# Sheet1.net
KiCad netlist of a schematic drawn in Altium Designer
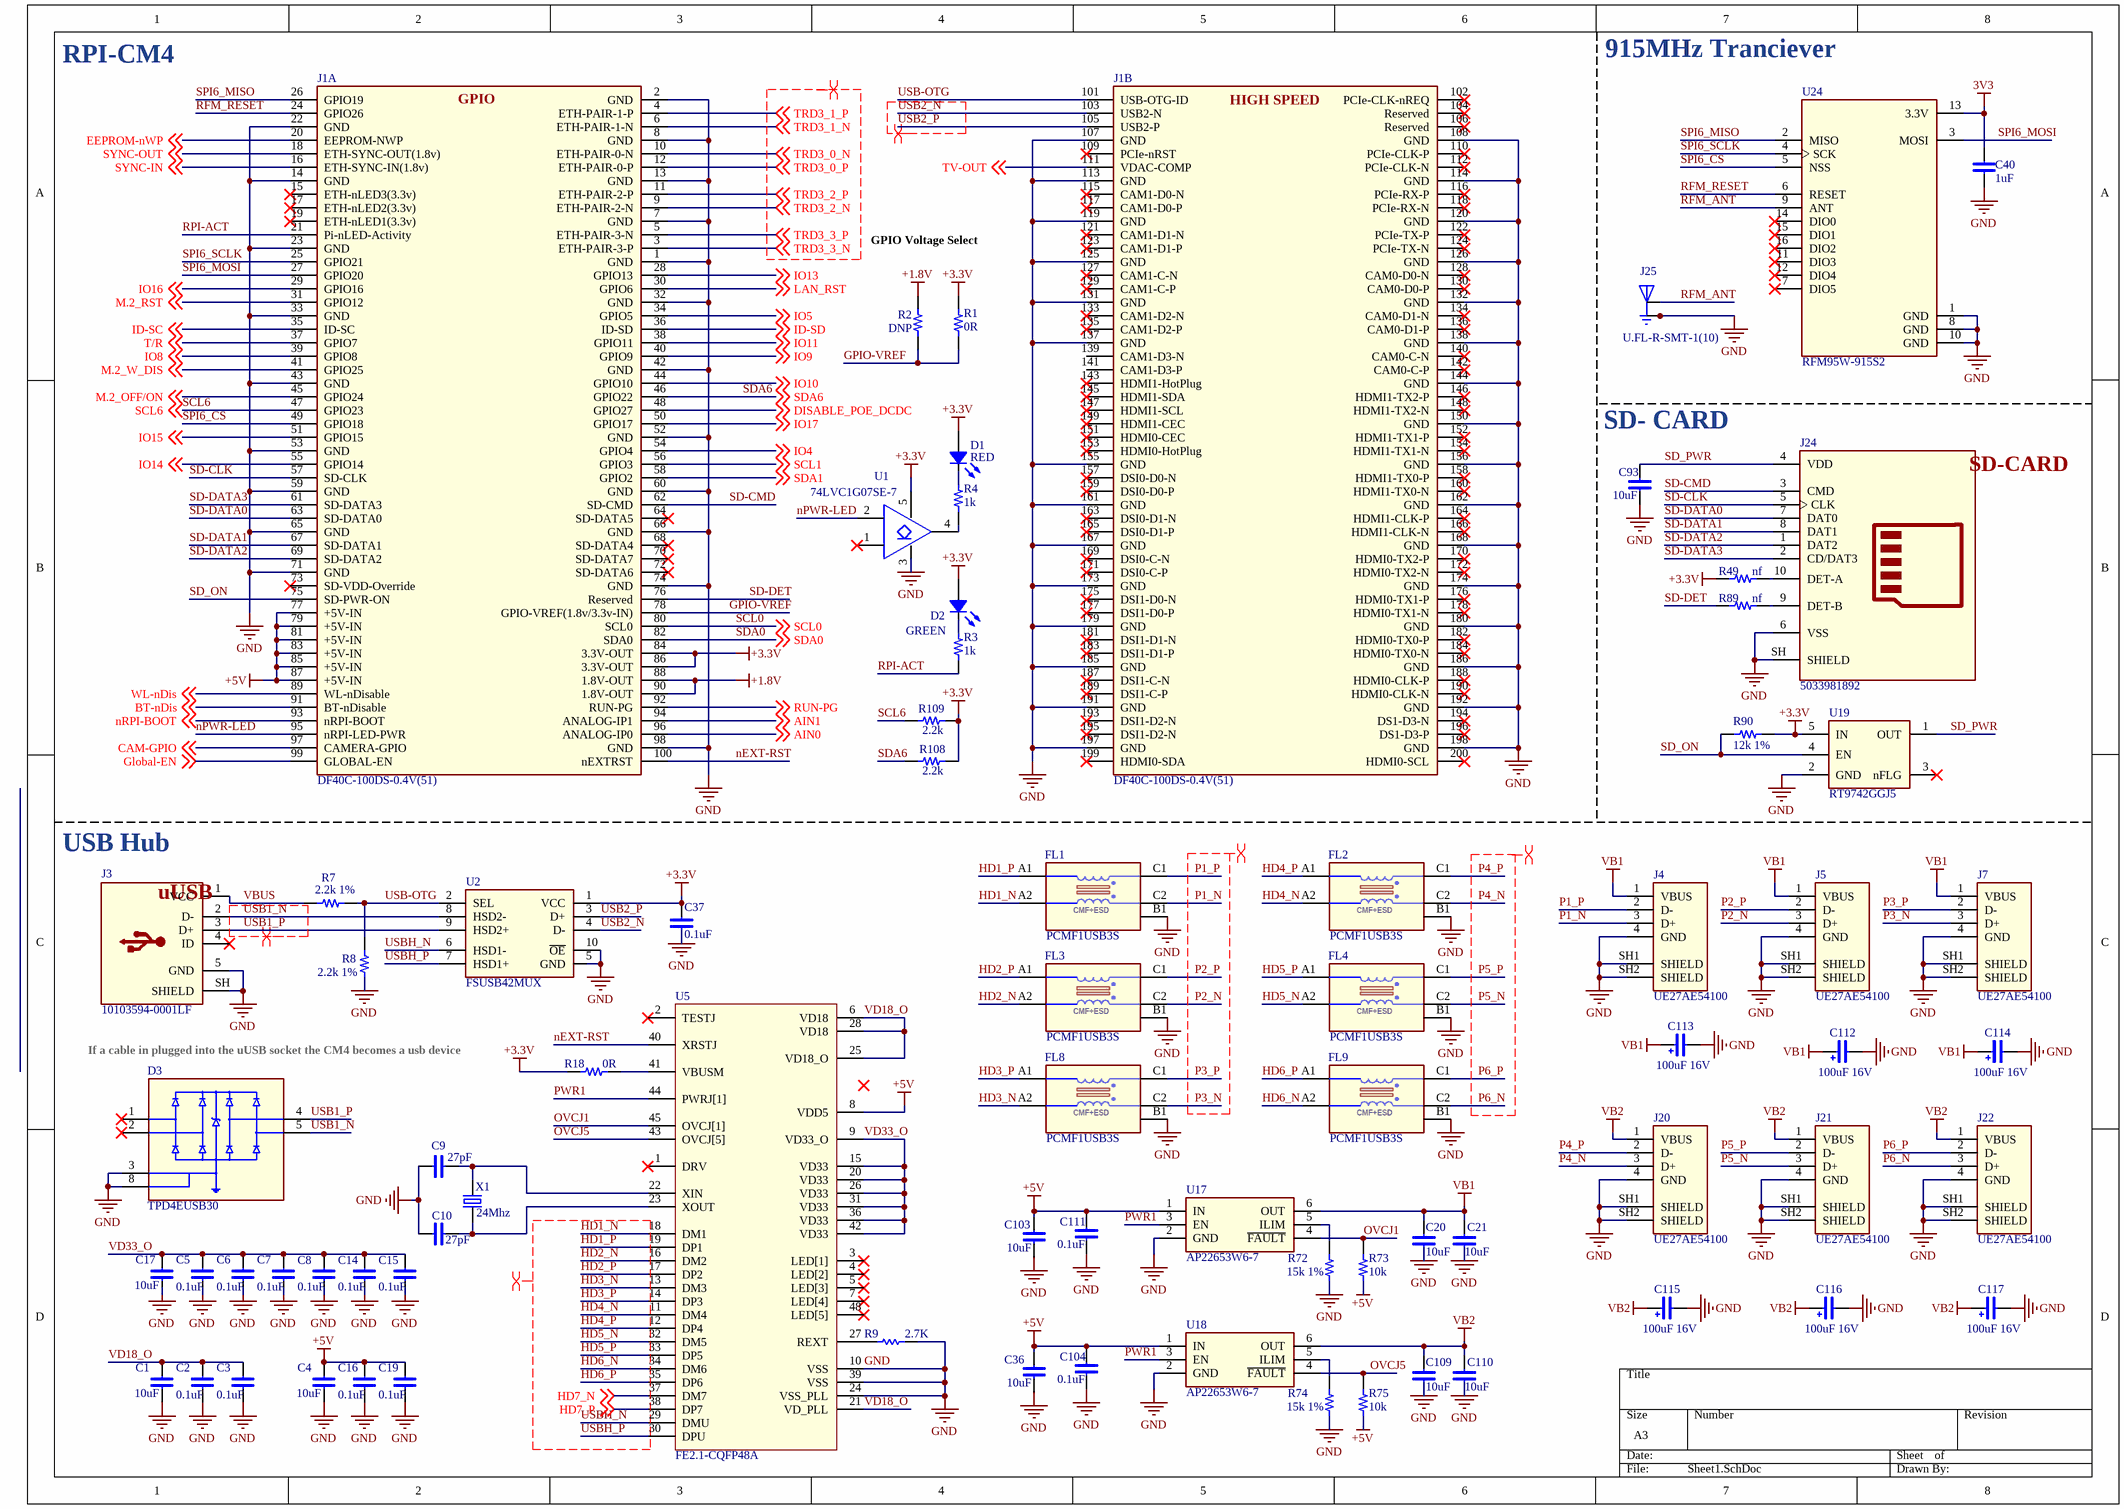
[diagram p0: Sheet1.SchDoc]

(export (version "E")
  (design (tool "Eeschema 10.0.6"))
  (components
    (comp (ref "C1")
      (value "10uF")
      (footprint "C-0603/1608")
      (description "CAP CER 10UF 10V X7R 0805")
      (fields (field (name "MFR. PART NO.") "GRM21BR71A106KA73K"))
      (libsource (lib "Custom_Library") (part "Capacitor-NonPolar"))
    )
    (comp (ref "C2")
      (value "0.1uF")
      (footprint "C-0402/1005")
      (description "CAP CER 0.1UF 16V X7R 0402")
      (fields (field (name "MFR. PART NO.") "GCM155R71C104KA55D"))
      (libsource (lib "Custom_Library") (part "Capacitor-NonPolar"))
    )
    (comp (ref "C3")
      (value "0.1uF")
      (footprint "C-0402/1005")
      (description "CAP CER 0.1UF 16V X7R 0402")
      (fields (field (name "MFR. PART NO.") "GCM155R71C104KA55D"))
      (libsource (lib "Custom_Library") (part "Capacitor-NonPolar"))
    )
    (comp (ref "C4")
      (value "10uF")
      (footprint "C-0603/1608")
      (description "CAP CER 10UF 10V X7R 0805")
      (fields (field (name "MFR. PART NO.") "GRM21BR71A106KA73K"))
      (libsource (lib "Custom_Library") (part "Capacitor-NonPolar"))
    )
    (comp (ref "C5")
      (value "0.1uF")
      (footprint "C-0402/1005")
      (description "CAP CER 0.1UF 16V X7R 0402")
      (fields (field (name "MFR. PART NO.") "GCM155R71C104KA55D"))
      (libsource (lib "Custom_Library") (part "Capacitor-NonPolar"))
    )
    (comp (ref "C6")
      (value "0.1uF")
      (footprint "C-0402/1005")
      (description "CAP CER 0.1UF 16V X7R 0402")
      (fields (field (name "MFR. PART NO.") "GCM155R71C104KA55D"))
      (libsource (lib "Custom_Library") (part "Capacitor-NonPolar"))
    )
    (comp (ref "C7")
      (value "0.1uF")
      (footprint "C-0402/1005")
      (description "CAP CER 0.1UF 16V X7R 0402")
      (fields (field (name "MFR. PART NO.") "GCM155R71C104KA55D"))
      (libsource (lib "Custom_Library") (part "Capacitor-NonPolar"))
    )
    (comp (ref "C8")
      (value "0.1uF")
      (footprint "C-0402/1005")
      (description "CAP CER 0.1UF 16V X7R 0402")
      (fields (field (name "MFR. PART NO.") "GCM155R71C104KA55D"))
      (libsource (lib "Custom_Library") (part "Capacitor-NonPolar"))
    )
    (comp (ref "C9")
      (value "27pF")
      (footprint "C-0402/1005")
      (description "CAP CER 27PF 50V CH 0402")
      (fields (field (name "MFR. PART NO.") "UMK105CH270JVHF"))
      (libsource (lib "DVT2 Library") (part "Capacitor-NonPolar"))
    )
    (comp (ref "C10")
      (value "27pF")
      (footprint "C-0402/1005")
      (description "CAP CER 27PF 50V CH 0402")
      (fields (field (name "MFR. PART NO.") "UMK105CH270JVHF"))
      (libsource (lib "DVT2 Library") (part "Capacitor-NonPolar"))
    )
    (comp (ref "C14")
      (value "0.1uF")
      (footprint "C-0402/1005")
      (description "CAP CER 0.1UF 16V X7R 0402")
      (fields (field (name "MFR. PART NO.") "GCM155R71C104KA55D"))
      (libsource (lib "Custom_Library") (part "Capacitor-NonPolar"))
    )
    (comp (ref "C15")
      (value "0.1uF")
      (footprint "C-0402/1005")
      (description "CAP CER 0.1UF 16V X7R 0402")
      (fields (field (name "MFR. PART NO.") "GCM155R71C104KA55D"))
      (libsource (lib "Custom_Library") (part "Capacitor-NonPolar"))
    )
    (comp (ref "C16")
      (value "0.1uF")
      (footprint "C-0402/1005")
      (description "CAP CER 0.1UF 16V X7R 0402")
      (fields (field (name "MFR. PART NO.") "GCM155R71C104KA55D"))
      (libsource (lib "Custom_Library") (part "Capacitor-NonPolar"))
    )
    (comp (ref "C17")
      (value "10uF")
      (footprint "C-0603/1608")
      (description "CAP CER 10UF 10V X7R 0805")
      (fields (field (name "MFR. PART NO.") "GRM21BR71A106KA73K"))
      (libsource (lib "Custom_Library") (part "Capacitor-NonPolar"))
    )
    (comp (ref "C19")
      (value "0.1uF")
      (footprint "C-0402/1005")
      (description "CAP CER 0.1UF 16V X7R 0402")
      (fields (field (name "MFR. PART NO.") "GCM155R71C104KA55D"))
      (libsource (lib "Custom_Library") (part "Capacitor-NonPolar"))
    )
    (comp (ref "C20")
      (value "10uF")
      (footprint "C-0603/1608")
      (description "CAP CER 10UF 10V X7R 0805")
      (fields (field (name "MFR. PART NO.") "GRM21BR71A106KA73K"))
      (libsource (lib "Custom_Library") (part "Capacitor-NonPolar"))
    )
    (comp (ref "C21")
      (value "10uF")
      (footprint "C-0603/1608")
      (description "CAP CER 10UF 10V X7R 0805")
      (fields (field (name "MFR. PART NO.") "GRM21BR71A106KA73K"))
      (libsource (lib "Custom_Library") (part "Capacitor-NonPolar"))
    )
    (comp (ref "C36")
      (value "10uF")
      (footprint "C-0603/1608")
      (description "CAP CER 10UF 10V X7R 0805")
      (fields (field (name "MFR. PART NO.") "GRM21BR71A106KA73K"))
      (libsource (lib "Custom_Library") (part "Capacitor-NonPolar"))
    )
    (comp (ref "C37")
      (value "0.1uF")
      (footprint "C-0402/1005")
      (description "CAP CER 0.1UF 16V X7R 0402")
      (fields (field (name "MFR. PART NO.") "GCM155R71C104KA55D"))
      (libsource (lib "Custom_Library") (part "Capacitor-NonPolar"))
    )
    (comp (ref "C40")
      (value "1uF")
      (footprint "C-0402/1005")
      (description "CAP CER 0.1UF 50V X7R 0402")
      (fields (field (name "MFR. PART NO.") "UMK105B7104KV-FR"))
      (libsource (lib "Custom_Library") (part "Capacitor-NonPolar"))
    )
    (comp (ref "C93")
      (value "10uF")
      (footprint "C-0805/2012")
      (description "CAP CER 10UF 10V X7R 0805")
      (fields (field (name "MFR. PART NO.") "GRM21BR71A106KA73K"))
      (libsource (lib "Custom_Library") (part "Capacitor-NonPolar"))
    )
    (comp (ref "C103")
      (value "10uF")
      (footprint "C-0603/1608")
      (description "CAP CER 10UF 10V X7R 0805")
      (fields (field (name "MFR. PART NO.") "GRM21BR71A106KA73K"))
      (libsource (lib "Custom_Library") (part "Capacitor-NonPolar"))
    )
    (comp (ref "C104")
      (value "0.1uF")
      (footprint "C-0402/1005")
      (description "CAP CER 0.1UF 16V X7R 0402")
      (fields (field (name "MFR. PART NO.") "GCM155R71C104KA55D"))
      (libsource (lib "Custom_Library") (part "Capacitor-NonPolar"))
    )
    (comp (ref "C109")
      (value "10uF")
      (footprint "C-0603/1608")
      (description "CAP CER 10UF 10V X7R 0805")
      (fields (field (name "MFR. PART NO.") "GRM21BR71A106KA73K"))
      (libsource (lib "Custom_Library") (part "Capacitor-NonPolar"))
    )
    (comp (ref "C110")
      (value "10uF")
      (footprint "C-0603/1608")
      (description "CAP CER 10UF 10V X7R 0805")
      (fields (field (name "MFR. PART NO.") "GRM21BR71A106KA73K"))
      (libsource (lib "Custom_Library") (part "Capacitor-NonPolar"))
    )
    (comp (ref "C111")
      (value "0.1uF")
      (footprint "C-0402/1005")
      (description "CAP CER 0.1UF 16V X7R 0402")
      (fields (field (name "MFR. PART NO.") "GCM155R71C104KA55D"))
      (libsource (lib "Custom_Library") (part "Capacitor-NonPolar"))
    )
    (comp (ref "C112")
      (value "100uF 16V")
      (footprint "CAP-TAN-2312")
      (description "CAP TANT 10UF 10% 16V 1206")
      (fields (field (name "MFR. PART NO.") "F931C106KAAAJ6"))
      (libsource (lib "Custom_Library") (part "Capacitor-Polar"))
    )
    (comp (ref "C113")
      (value "100uF 16V")
      (footprint "CAP-TAN-2312")
      (description "CAP TANT 10UF 10% 16V 1206")
      (fields (field (name "MFR. PART NO.") "F931C106KAAAJ6"))
      (libsource (lib "Custom_Library") (part "Capacitor-Polar"))
    )
    (comp (ref "C114")
      (value "100uF 16V")
      (footprint "CAP-TAN-2312")
      (description "CAP TANT 10UF 10% 16V 1206")
      (fields (field (name "MFR. PART NO.") "F931C106KAAAJ6"))
      (libsource (lib "Custom_Library") (part "Capacitor-Polar"))
    )
    (comp (ref "C115")
      (value "100uF 16V")
      (footprint "CAP-TAN-2312")
      (description "CAP TANT 10UF 10% 16V 1206")
      (fields (field (name "MFR. PART NO.") "F931C106KAAAJ6"))
      (libsource (lib "Custom_Library") (part "Capacitor-Polar"))
    )
    (comp (ref "C116")
      (value "100uF 16V")
      (footprint "CAP-TAN-2312")
      (description "CAP TANT 10UF 10% 16V 1206")
      (fields (field (name "MFR. PART NO.") "F931C106KAAAJ6"))
      (libsource (lib "Custom_Library") (part "Capacitor-Polar"))
    )
    (comp (ref "C117")
      (value "100uF 16V")
      (footprint "CAP-TAN-2312")
      (description "CAP TANT 10UF 10% 16V 1206")
      (fields (field (name "MFR. PART NO.") "F931C106KAAAJ6"))
      (libsource (lib "Custom_Library") (part "Capacitor-Polar"))
    )
    (comp (ref "D1")
      (value "RED")
      (footprint "LED-0603-RED")
      (description "LED RED CLEAR CHIP SMD R/A")
      (fields (field (name "MFR. PART NO.") "LTST-S270KRKT"))
      (libsource (lib "Diodes") (part "LED SMD"))
    )
    (comp (ref "D2")
      (value "GREEN")
      (footprint "LED-0603-Green")
      (description "LED GREEN CLEAR CHIP SMD R/A")
      (fields (field (name "MFR. PART NO.") "LTST-S270KGKT"))
      (libsource (lib "Diodes") (part "LED SMD"))
    )
    (comp (ref "D3")
      (value "TPD4EUSB30")
      (footprint "10-USON (2.5x1)")
      (description "TVS DIODE 5.5V 8V 10USON")
      (fields (field (name "MFR. PART NO.") "TPD4EUSB30DQAR"))
      (libsource (lib "Custom_Library") (part "TPD4EUSB30"))
    )
    (comp (ref "FL1")
      (value "PCMF1USB3S")
      (footprint "WLCSP5(2-1-2)_NEX")
      (description "FLT, SMT, WLCSP5, Common Mode EMI Filters")
      (fields (field (name "MANUFACTURER") "Nexperia"))
      (libsource (lib "Ewikenheiser_CM4_Board_V2") (part "Nexperia, PCMF1USB3SZ"))
    )
    (comp (ref "FL2")
      (value "PCMF1USB3S")
      (footprint "WLCSP5(2-1-2)_NEX")
      (description "FLT, SMT, WLCSP5, Common Mode EMI Filters")
      (fields (field (name "MANUFACTURER") "Nexperia"))
      (libsource (lib "Ewikenheiser_CM4_Board_V2") (part "Nexperia, PCMF1USB3SZ"))
    )
    (comp (ref "FL3")
      (value "PCMF1USB3S")
      (footprint "WLCSP5(2-1-2)_NEX")
      (description "FLT, SMT, WLCSP5, Common Mode EMI Filters")
      (fields (field (name "MANUFACTURER") "Nexperia"))
      (libsource (lib "Ewikenheiser_CM4_Board_V2") (part "Nexperia, PCMF1USB3SZ"))
    )
    (comp (ref "FL4")
      (value "PCMF1USB3S")
      (footprint "WLCSP5(2-1-2)_NEX")
      (description "FLT, SMT, WLCSP5, Common Mode EMI Filters")
      (fields (field (name "MANUFACTURER") "Nexperia"))
      (libsource (lib "Ewikenheiser_CM4_Board_V2") (part "Nexperia, PCMF1USB3SZ"))
    )
    (comp (ref "FL8")
      (value "PCMF1USB3S")
      (footprint "WLCSP5(2-1-2)_NEX")
      (description "FLT, SMT, WLCSP5, Common Mode EMI Filters")
      (fields (field (name "MANUFACTURER") "Nexperia"))
      (libsource (lib "Ewikenheiser_CM4_Board_V2") (part "Nexperia, PCMF1USB3SZ"))
    )
    (comp (ref "FL9")
      (value "PCMF1USB3S")
      (footprint "WLCSP5(2-1-2)_NEX")
      (description "FLT, SMT, WLCSP5, Common Mode EMI Filters")
      (fields (field (name "MANUFACTURER") "Nexperia"))
      (libsource (lib "Ewikenheiser_CM4_Board_V2") (part "Nexperia, PCMF1USB3SZ"))
    )
    (comp (ref "J1")
      (value "DF40C-100DS-0.4V(51)")
      (footprint "RPI-CM4")
      (description "CONN RCPT 100POS SMD GOLD")
      (libsource (lib "Custom_Library") (part "RPICM4"))
    )
    (comp (ref "J3")
      (value "10103594-0001LF")
      (footprint "USB-micro")
      (description "CONN RCPT USB2.0 MICRO B SMD R/A")
      (libsource (lib "Custom_Library") (part "USB-Micro"))
    )
    (comp (ref "J4")
      (value "UE27AE54100")
      (footprint "AMPHENOL_UE27AE54100")
      (fields (field (name "MF") "{'manufacturer': u'Amphenol ICC (Commercial Products)'}"))
      (libsource (lib "UE27AE54100") (part "UE27AE54100"))
    )
    (comp (ref "J5")
      (value "UE27AE54100")
      (footprint "AMPHENOL_UE27AE54100")
      (fields (field (name "MF") "{'manufacturer': u'Amphenol ICC (Commercial Products)'}"))
      (libsource (lib "UE27AE54100") (part "UE27AE54100"))
    )
    (comp (ref "J7")
      (value "UE27AE54100")
      (footprint "AMPHENOL_UE27AE54100")
      (fields (field (name "MF") "{'manufacturer': u'Amphenol ICC (Commercial Products)'}"))
      (libsource (lib "UE27AE54100") (part "UE27AE54100"))
    )
    (comp (ref "J20")
      (value "UE27AE54100")
      (footprint "AMPHENOL_UE27AE54100")
      (fields (field (name "MF") "{'manufacturer': u'Amphenol ICC (Commercial Products)'}"))
      (libsource (lib "UE27AE54100") (part "UE27AE54100"))
    )
    (comp (ref "J21")
      (value "UE27AE54100")
      (footprint "AMPHENOL_UE27AE54100")
      (fields (field (name "MF") "{'manufacturer': u'Amphenol ICC (Commercial Products)'}"))
      (libsource (lib "UE27AE54100") (part "UE27AE54100"))
    )
    (comp (ref "J22")
      (value "UE27AE54100")
      (footprint "AMPHENOL_UE27AE54100")
      (fields (field (name "MF") "{'manufacturer': u'Amphenol ICC (Commercial Products)'}"))
      (libsource (lib "UE27AE54100") (part "UE27AE54100"))
    )
    (comp (ref "J24")
      (value "5033981892")
      (footprint "MOLEX-503398-1892")
      (description "MICRO SD PUSH/PUSH SMALL 8C")
      (libsource (lib "Custom_Library") (part "SD-CARD"))
    )
    (comp (ref "J25")
      (value "U.FL-R-SMT-1(10)")
      (footprint "HRS_U.FL-R-SMT-1(10)")
      (description "U.FL Series 6 Ghz 50 Ohm Ultra-small SMT Coaxial Cable Receptacle")
      (libsource (lib "U.FL-R-SMT-1(10)") (part "U.FL-R-SMT-1(10)"))
    )
    (comp (ref "R1")
      (value "0R")
      (footprint "R-0603/1608")
      (description "RESA-AS 0805 0R JUMPER 125MW")
      (fields (field (name "MFR. PART NO.") "CR0805AJ/-000EAS"))
      (libsource (lib "Custom_Library") (part "Resistor"))
    )
    (comp (ref "R2")
      (value "DNP")
      (footprint "R-0603/1608")
      (description "CRGCQ 0402 470R 1%")
      (fields (field (name "MFR. PART NO.") "nf"))
      (libsource (lib "Custom_Library") (part "Resistor"))
    )
    (comp (ref "R3")
      (value "1k")
      (footprint "R-0402/1005")
      (description "RES SMD 1K OHM 1% 1/16W 0402")
      (fields (field (name "MFR. PART NO.") "RC0402FR-071KL"))
      (libsource (lib "Custom_Library") (part "Resistor"))
    )
    (comp (ref "R4")
      (value "1k")
      (footprint "R-0402/1005")
      (description "RES SMD 1K OHM 1% 1/16W 0402")
      (fields (field (name "MFR. PART NO.") "RC0402FR-071KL"))
      (libsource (lib "Custom_Library") (part "Resistor"))
    )
    (comp (ref "R7")
      (value "2.2k 1%")
      (footprint "R-0402/1005")
      (description "RES SMD 2.2K OHM 1% 1/16W 0402")
      (fields (field (name "MFR. PART NO.") "RT0402FRE072K2L"))
      (libsource (lib "Custom_Library") (part "Resistor"))
    )
    (comp (ref "R8")
      (value "2.2k 1%")
      (footprint "R-0402/1005")
      (description "RES SMD 2.2K OHM 1% 1/16W 0402")
      (fields (field (name "MFR. PART NO.") "RT0402FRE072K2L"))
      (libsource (lib "Custom_Library") (part "Resistor"))
    )
    (comp (ref "R9")
      (value "2.7K")
      (footprint "R-0402/1005")
      (description "Resistor")
      (fields (field (name "PUBLISHER") "Altium Limited"))
      (libsource (lib "Miscellaneous Devices") (part "Res1"))
    )
    (comp (ref "R18")
      (value "0R")
      (footprint "R-0402/1005")
      (description "RES SMD 2.2K OHM 1% 1/16W 0402")
      (fields (field (name "MFR. PART NO.") "RT0402FRE072K2L"))
      (libsource (lib "Custom_Library") (part "Resistor"))
    )
    (comp (ref "R49")
      (value "nf")
      (footprint "R-0402/1005")
      (description "RES SMD 1K OHM 1% 1/16W 0402")
      (fields (field (name "MFR. PART NO.") "RC0402FR-071KL"))
      (libsource (lib "Custom_Library") (part "Resistor"))
    )
    (comp (ref "R72")
      (value "15k 1%")
      (footprint "R-0402/1005")
      (description "RES SMD 15K OHM 1% 1/16W 0402")
      (fields (field (name "MFR. PART NO.") "MCR01MZPF1502"))
      (libsource (lib "Custom_Library") (part "Resistor"))
    )
    (comp (ref "R73")
      (value "10k")
      (footprint "R-0402/1005")
      (description "RES SMD 1K OHM 1% 1/16W 0402")
      (fields (field (name "MFR. PART NO.") "RC0402FR-071KL"))
      (libsource (lib "Custom_Library") (part "Resistor"))
    )
    (comp (ref "R74")
      (value "15k 1%")
      (footprint "R-0402/1005")
      (description "RES SMD 15K OHM 1% 1/16W 0402")
      (fields (field (name "MFR. PART NO.") "MCR01MZPF1502"))
      (libsource (lib "Custom_Library") (part "Resistor"))
    )
    (comp (ref "R75")
      (value "10k")
      (footprint "R-0402/1005")
      (description "RES SMD 1K OHM 1% 1/16W 0402")
      (fields (field (name "MFR. PART NO.") "RC0402FR-071KL"))
      (libsource (lib "Custom_Library") (part "Resistor"))
    )
    (comp (ref "R89")
      (value "nf")
      (footprint "R-0402/1005")
      (description "RES SMD 1K OHM 1% 1/16W 0402")
      (fields (field (name "MFR. PART NO.") "RC0402FR-071KL"))
      (libsource (lib "Custom_Library") (part "Resistor"))
    )
    (comp (ref "R90")
      (value "12k 1%")
      (footprint "R-0402/1005")
      (description "RES SMD 12K OHM 1% 1/16W 0402")
      (fields (field (name "MFR. PART NO.") "MCR01MZPF1202"))
      (libsource (lib "Custom_Library") (part "Resistor"))
    )
    (comp (ref "R108")
      (value "2.2k")
      (footprint "R-0402/1005")
      (description "RES SMD 1K OHM 1% 1/16W 0402")
      (fields (field (name "MFR. PART NO.") "RC0402FR-071KL"))
      (libsource (lib "Custom_Library") (part "Resistor"))
    )
    (comp (ref "R109")
      (value "2.2k")
      (footprint "R-0402/1005")
      (description "RES SMD 1K OHM 1% 1/16W 0402")
      (fields (field (name "MFR. PART NO.") "RC0402FR-071KL"))
      (libsource (lib "Custom_Library") (part "Resistor"))
    )
    (comp (ref "U1")
      (value "74LVC1G07SE-7")
      (footprint "SOT-353")
      (description "IC BUF NON-INVERT 5.5V SOT353")
      (libsource (lib "Custom_Library") (part "74LVC1G07SE-7"))
    )
    (comp (ref "U2")
      (value "FSUSB42MUX")
      (footprint "10-MSOP-W3.0mm")
      (description "IC USB SWITCH DPDT 10MSOP")
      (libsource (lib "Custom_Library") (part "FSUSB42MUX"))
    )
    (comp (ref "U5")
      (value "FE2.1-CQFP48A")
      (footprint "PCBComponent_1")
      (libsource (lib "FE2.1-CQFP48A") (part "Component_1"))
    )
    (comp (ref "U17")
      (value "AP22653W6-7")
      (footprint "SOT-23-6")
      (description "LOAD SWITCH,SOT26,T&R,3K")
      (libsource (lib "Custom_Library") (part "AP22653W6-7"))
    )
    (comp (ref "U18")
      (value "AP22653W6-7")
      (footprint "SOT-23-6")
      (description "LOAD SWITCH,SOT26,T&R,3K")
      (libsource (lib "Custom_Library") (part "AP22653W6-7"))
    )
    (comp (ref "U19")
      (value "RT9742GGJ5")
      (footprint "SOT-23-5")
      (description "IC PWR SWTCH N-CHAN 1:1 TSOT23-5")
      (libsource (lib "Custom_Library") (part "RT9742GGJ5"))
    )
    (comp (ref "U24")
      (value "RFM95W-915S2")
      (footprint "XCVR_RFM95W-915S2")
      (description "RFM95(W) - Low Power Long Range Transceiver Module V1.0")
      (libsource (lib "RFM95W-915S2") (part "RFM95W-915S2"))
    )
    (comp (ref "X1")
      (value "24Mhz")
      (footprint "HC-49/US")
      (description "CRYSTAL 24.0000MHZ 18PF TH")
      (fields (field (name "MFR. PART NO.") "ECS-240-18-4XEN"))
      (libsource (lib "Oscilators") (part "ST3215SB32768C0HPWBB"))
    )
  )
  (nets
    (net (code "1") (name "+1.8V") (class "Default")
      (node (ref "J1") (pin "88") (pinfunction "1.8V-OUT_88") (pintype "passive"))
      (node (ref "J1") (pin "90") (pinfunction "1.8V-OUT_90") (pintype "passive"))
      (node (ref "R2") (pin "2") (pinfunction "2_2") (pintype "passive"))
    )
    (net (code "2") (name "+3.3V") (class "Default")
      (node (ref "C37") (pin "1") (pinfunction "1_1") (pintype "passive"))
      (node (ref "D1") (pin "1") (pinfunction "1_1") (pintype "passive"))
      (node (ref "D2") (pin "1") (pinfunction "1_1") (pintype "passive"))
      (node (ref "J1") (pin "84") (pinfunction "3.3V-OUT_84") (pintype "passive"))
      (node (ref "J1") (pin "86") (pinfunction "3.3V-OUT_86") (pintype "passive"))
      (node (ref "R1") (pin "2") (pinfunction "2_2") (pintype "passive"))
      (node (ref "R108") (pin "1") (pinfunction "1_1") (pintype "passive"))
      (node (ref "R109") (pin "1") (pinfunction "1_1") (pintype "passive"))
      (node (ref "R18") (pin "1") (pinfunction "1_1") (pintype "passive"))
      (node (ref "R49") (pin "2") (pinfunction "2_2") (pintype "passive"))
      (node (ref "R90") (pin "1") (pinfunction "1_1") (pintype "passive"))
      (node (ref "U1") (pin "5") (pinfunction "5_5") (pintype "passive"))
      (node (ref "U19") (pin "5") (pinfunction "IN_5") (pintype "passive"))
      (node (ref "U2") (pin "1") (pinfunction "VCC_1") (pintype "passive"))
    )
    (net (code "3") (name "+5V") (class "Default")
      (node (ref "C103") (pin "1") (pinfunction "1_1") (pintype "passive"))
      (node (ref "C104") (pin "1") (pinfunction "1_1") (pintype "passive"))
      (node (ref "C111") (pin "1") (pinfunction "1_1") (pintype "passive"))
      (node (ref "C16") (pin "1") (pinfunction "1_1") (pintype "passive"))
      (node (ref "C19") (pin "1") (pinfunction "1_1") (pintype "passive"))
      (node (ref "C36") (pin "1") (pinfunction "1_1") (pintype "passive"))
      (node (ref "C4") (pin "1") (pinfunction "1_1") (pintype "passive"))
      (node (ref "J1") (pin "77") (pinfunction "+5V-IN_77") (pintype "passive"))
      (node (ref "J1") (pin "79") (pinfunction "+5V-IN_79") (pintype "passive"))
      (node (ref "J1") (pin "81") (pinfunction "+5V-IN_81") (pintype "passive"))
      (node (ref "J1") (pin "83") (pinfunction "+5V-IN_83") (pintype "passive"))
      (node (ref "J1") (pin "85") (pinfunction "+5V-IN_85") (pintype "passive"))
      (node (ref "J1") (pin "87") (pinfunction "+5V-IN_87") (pintype "passive"))
      (node (ref "R73") (pin "2") (pinfunction "2_2") (pintype "passive"))
      (node (ref "R75") (pin "2") (pinfunction "2_2") (pintype "passive"))
      (node (ref "U17") (pin "1") (pinfunction "IN_1") (pintype "passive"))
      (node (ref "U18") (pin "1") (pinfunction "IN_1") (pintype "passive"))
      (node (ref "U5") (pin "8") (pinfunction "VDD5_8") (pintype "passive"))
    )
    (net (code "4") (name "/GPIO-VREF") (class "Default")
      (node (ref "J1") (pin "78") (pinfunction "GPIO-VREF(1.8v/3.3v-IN)_78") (pintype "passive"))
      (node (ref "R1") (pin "1") (pinfunction "1_1") (pintype "passive"))
      (node (ref "R2") (pin "1") (pinfunction "1_1") (pintype "passive"))
    )
    (net (code "5") (name "/HD1_N") (class "Default")
      (node (ref "FL1") (pin "A2") (pinfunction "CH1_IN-_A2") (pintype "passive"))
      (node (ref "U5") (pin "18") (pinfunction "DM1_18") (pintype "passive"))
    )
    (net (code "6") (name "/HD1_P") (class "Default")
      (node (ref "FL1") (pin "A1") (pinfunction "CH1_IN+_A1") (pintype "passive"))
      (node (ref "U5") (pin "19") (pinfunction "DP1_19") (pintype "passive"))
    )
    (net (code "7") (name "/HD2_N") (class "Default")
      (node (ref "FL3") (pin "A2") (pinfunction "CH1_IN-_A2") (pintype "passive"))
      (node (ref "U5") (pin "16") (pinfunction "DM2_16") (pintype "passive"))
    )
    (net (code "8") (name "/HD2_P") (class "Default")
      (node (ref "FL3") (pin "A1") (pinfunction "CH1_IN+_A1") (pintype "passive"))
      (node (ref "U5") (pin "17") (pinfunction "DP2_17") (pintype "passive"))
    )
    (net (code "9") (name "/HD3_N") (class "Default")
      (node (ref "FL8") (pin "A2") (pinfunction "CH1_IN-_A2") (pintype "passive"))
      (node (ref "U5") (pin "13") (pinfunction "DM3_13") (pintype "passive"))
    )
    (net (code "10") (name "/HD3_P") (class "Default")
      (node (ref "FL8") (pin "A1") (pinfunction "CH1_IN+_A1") (pintype "passive"))
      (node (ref "U5") (pin "14") (pinfunction "DP3_14") (pintype "passive"))
    )
    (net (code "11") (name "/HD4_N") (class "Default")
      (node (ref "FL2") (pin "A2") (pinfunction "CH1_IN-_A2") (pintype "passive"))
      (node (ref "U5") (pin "11") (pinfunction "DM4_11") (pintype "passive"))
    )
    (net (code "12") (name "/HD4_P") (class "Default")
      (node (ref "FL2") (pin "A1") (pinfunction "CH1_IN+_A1") (pintype "passive"))
      (node (ref "U5") (pin "12") (pinfunction "DP4_12") (pintype "passive"))
    )
    (net (code "13") (name "/HD5_N") (class "Default")
      (node (ref "FL4") (pin "A2") (pinfunction "CH1_IN-_A2") (pintype "passive"))
      (node (ref "U5") (pin "32") (pinfunction "DM5_32") (pintype "passive"))
    )
    (net (code "14") (name "/HD5_P") (class "Default")
      (node (ref "FL4") (pin "A1") (pinfunction "CH1_IN+_A1") (pintype "passive"))
      (node (ref "U5") (pin "33") (pinfunction "DP5_33") (pintype "passive"))
    )
    (net (code "15") (name "/HD6_N") (class "Default")
      (node (ref "FL9") (pin "A2") (pinfunction "CH1_IN-_A2") (pintype "passive"))
      (node (ref "U5") (pin "34") (pinfunction "DM6_34") (pintype "passive"))
    )
    (net (code "16") (name "/HD6_P") (class "Default")
      (node (ref "FL9") (pin "A1") (pinfunction "CH1_IN+_A1") (pintype "passive"))
      (node (ref "U5") (pin "35") (pinfunction "DP6_35") (pintype "passive"))
    )
    (net (code "17") (name "/OVCJ1") (class "Default")
      (node (ref "R73") (pin "1") (pinfunction "1_1") (pintype "passive"))
      (node (ref "U17") (pin "4") (pinfunction "~{FAULT}_4") (pintype "passive"))
      (node (ref "U5") (pin "45") (pinfunction "OVCJ[1]_45") (pintype "passive"))
    )
    (net (code "18") (name "/OVCJ5") (class "Default")
      (node (ref "R75") (pin "1") (pinfunction "1_1") (pintype "passive"))
      (node (ref "U18") (pin "4") (pinfunction "~{FAULT}_4") (pintype "passive"))
      (node (ref "U5") (pin "43") (pinfunction "OVCJ[5]_43") (pintype "passive"))
    )
    (net (code "19") (name "/P1_N") (class "Default")
      (node (ref "FL1") (pin "C2") (pinfunction "CH1_OUT-_C2") (pintype "passive"))
      (node (ref "J4") (pin "3") (pinfunction "D+_3") (pintype "passive"))
    )
    (net (code "20") (name "/P1_P") (class "Default")
      (node (ref "FL1") (pin "C1") (pinfunction "CH1_OUT+_C1") (pintype "passive"))
      (node (ref "J4") (pin "2") (pinfunction "D-_2") (pintype "passive"))
    )
    (net (code "21") (name "/P2_N") (class "Default")
      (node (ref "FL3") (pin "C2") (pinfunction "CH1_OUT-_C2") (pintype "passive"))
      (node (ref "J5") (pin "3") (pinfunction "D+_3") (pintype "passive"))
    )
    (net (code "22") (name "/P2_P") (class "Default")
      (node (ref "FL3") (pin "C1") (pinfunction "CH1_OUT+_C1") (pintype "passive"))
      (node (ref "J5") (pin "2") (pinfunction "D-_2") (pintype "passive"))
    )
    (net (code "23") (name "/P3_N") (class "Default")
      (node (ref "FL8") (pin "C2") (pinfunction "CH1_OUT-_C2") (pintype "passive"))
      (node (ref "J7") (pin "3") (pinfunction "D+_3") (pintype "passive"))
    )
    (net (code "24") (name "/P3_P") (class "Default")
      (node (ref "FL8") (pin "C1") (pinfunction "CH1_OUT+_C1") (pintype "passive"))
      (node (ref "J7") (pin "2") (pinfunction "D-_2") (pintype "passive"))
    )
    (net (code "25") (name "/P4_N") (class "Default")
      (node (ref "FL2") (pin "C2") (pinfunction "CH1_OUT-_C2") (pintype "passive"))
      (node (ref "J20") (pin "3") (pinfunction "D+_3") (pintype "passive"))
    )
    (net (code "26") (name "/P4_P") (class "Default")
      (node (ref "FL2") (pin "C1") (pinfunction "CH1_OUT+_C1") (pintype "passive"))
      (node (ref "J20") (pin "2") (pinfunction "D-_2") (pintype "passive"))
    )
    (net (code "27") (name "/P5_N") (class "Default")
      (node (ref "FL4") (pin "C2") (pinfunction "CH1_OUT-_C2") (pintype "passive"))
      (node (ref "J21") (pin "3") (pinfunction "D+_3") (pintype "passive"))
    )
    (net (code "28") (name "/P5_P") (class "Default")
      (node (ref "FL4") (pin "C1") (pinfunction "CH1_OUT+_C1") (pintype "passive"))
      (node (ref "J21") (pin "2") (pinfunction "D-_2") (pintype "passive"))
    )
    (net (code "29") (name "/P6_N") (class "Default")
      (node (ref "FL9") (pin "C2") (pinfunction "CH1_OUT-_C2") (pintype "passive"))
      (node (ref "J22") (pin "3") (pinfunction "D+_3") (pintype "passive"))
    )
    (net (code "30") (name "/P6_P") (class "Default")
      (node (ref "FL9") (pin "C1") (pinfunction "CH1_OUT+_C1") (pintype "passive"))
      (node (ref "J22") (pin "2") (pinfunction "D-_2") (pintype "passive"))
    )
    (net (code "31") (name "/PWR1") (class "Default")
      (node (ref "U17") (pin "3") (pinfunction "EN_3") (pintype "passive"))
      (node (ref "U18") (pin "3") (pinfunction "EN_3") (pintype "passive"))
      (node (ref "U5") (pin "44") (pinfunction "PWRJ[1]_44") (pintype "passive"))
    )
    (net (code "32") (name "/RFM_ANT") (class "Default")
      (node (ref "J25") (pin "2") (pinfunction "SIG_2") (pintype "passive"))
      (node (ref "U24") (pin "9") (pinfunction "ANT_9") (pintype "passive"))
    )
    (net (code "33") (name "/RFM_RESET") (class "Default")
      (node (ref "J1") (pin "24") (pinfunction "GPIO26_24") (pintype "passive"))
      (node (ref "U24") (pin "6") (pinfunction "RESET_6") (pintype "passive"))
    )
    (net (code "34") (name "/RPI-ACT") (class "Default")
      (node (ref "J1") (pin "21") (pinfunction "Pi-nLED-Activity_21") (pintype "passive"))
      (node (ref "R3") (pin "2") (pinfunction "2_2") (pintype "passive"))
    )
    (net (code "35") (name "/SD-CLK") (class "Default")
      (node (ref "J1") (pin "57") (pinfunction "SD-CLK_57") (pintype "passive"))
      (node (ref "J24") (pin "5") (pinfunction "CLK_5") (pintype "passive"))
    )
    (net (code "36") (name "/SD-CMD") (class "Default")
      (node (ref "J1") (pin "62") (pinfunction "SD-CMD_62") (pintype "passive"))
      (node (ref "J24") (pin "3") (pinfunction "CMD_3") (pintype "passive"))
    )
    (net (code "37") (name "/SD-DATA0") (class "Default")
      (node (ref "J1") (pin "63") (pinfunction "SD-DATA0_63") (pintype "passive"))
      (node (ref "J24") (pin "7") (pinfunction "DAT0_7") (pintype "passive"))
    )
    (net (code "38") (name "/SD-DATA1") (class "Default")
      (node (ref "J1") (pin "67") (pinfunction "SD-DATA1_67") (pintype "passive"))
      (node (ref "J24") (pin "8") (pinfunction "DAT1_8") (pintype "passive"))
    )
    (net (code "39") (name "/SD-DATA2") (class "Default")
      (node (ref "J1") (pin "69") (pinfunction "SD-DATA2_69") (pintype "passive"))
      (node (ref "J24") (pin "1") (pinfunction "DAT2_1") (pintype "passive"))
    )
    (net (code "40") (name "/SD-DATA3") (class "Default")
      (node (ref "J1") (pin "61") (pinfunction "SD-DATA3_61") (pintype "passive"))
      (node (ref "J24") (pin "2") (pinfunction "CD/DAT3_2") (pintype "passive"))
    )
    (net (code "41") (name "/SD-DET") (class "Default")
      (node (ref "J1") (pin "76") (pinfunction "Reserved_76") (pintype "passive"))
      (node (ref "R89") (pin "2") (pinfunction "2_2") (pintype "passive"))
    )
    (net (code "42") (name "/SD_ON") (class "Default")
      (node (ref "J1") (pin "75") (pinfunction "SD-PWR-ON_75") (pintype "passive"))
      (node (ref "R90") (pin "2") (pinfunction "2_2") (pintype "passive"))
      (node (ref "U19") (pin "4") (pinfunction "EN_4") (pintype "passive"))
    )
    (net (code "43") (name "/SD_PWR") (class "Default")
      (node (ref "C93") (pin "1") (pinfunction "1_1") (pintype "passive"))
      (node (ref "J24") (pin "4") (pinfunction "VDD_4") (pintype "power_in"))
      (node (ref "U19") (pin "1") (pinfunction "OUT_1") (pintype "passive"))
    )
    (net (code "44") (name "/SPI6_CS") (class "Default")
      (node (ref "J1") (pin "49") (pinfunction "GPIO18_49") (pintype "passive"))
      (node (ref "U24") (pin "5") (pinfunction "NSS_5") (pintype "passive"))
    )
    (net (code "45") (name "/SPI6_MISO") (class "Default")
      (node (ref "J1") (pin "26") (pinfunction "GPIO19_26") (pintype "passive"))
      (node (ref "U24") (pin "2") (pinfunction "MISO_2") (pintype "passive"))
    )
    (net (code "46") (name "/SPI6_MOSI") (class "Default")
      (node (ref "J1") (pin "27") (pinfunction "GPIO20_27") (pintype "passive"))
      (node (ref "U24") (pin "3") (pinfunction "MOSI_3") (pintype "passive"))
    )
    (net (code "47") (name "/SPI6_SCLK") (class "Default")
      (node (ref "J1") (pin "25") (pinfunction "GPIO21_25") (pintype "passive"))
      (node (ref "U24") (pin "4") (pinfunction "SCK_4") (pintype "passive"))
    )
    (net (code "48") (name "/USB-OTG") (class "Default")
      (node (ref "J1") (pin "101") (pinfunction "USB-OTG-ID_101") (pintype "passive"))
      (node (ref "R7") (pin "1") (pinfunction "1_1") (pintype "passive"))
      (node (ref "R8") (pin "1") (pinfunction "1_1") (pintype "passive"))
      (node (ref "U2") (pin "2") (pinfunction "SEL_2") (pintype "passive"))
    )
    (net (code "49") (name "/USB1_N") (class "Default")
      (node (ref "D3") (pin "5") (pinfunction "D2-_5") (pintype "passive"))
      (node (ref "J3") (pin "2") (pinfunction "D-_2") (pintype "passive"))
      (node (ref "U2") (pin "8") (pinfunction "HSD2-_8") (pintype "passive"))
    )
    (net (code "50") (name "/USB1_P") (class "Default")
      (node (ref "D3") (pin "4") (pinfunction "D2+_4") (pintype "passive"))
      (node (ref "J3") (pin "3") (pinfunction "D+_3") (pintype "passive"))
      (node (ref "U2") (pin "9") (pinfunction "HSD2+_9") (pintype "passive"))
    )
    (net (code "51") (name "/USB2_N") (class "Default")
      (node (ref "J1") (pin "103") (pinfunction "USB2-N_103") (pintype "passive"))
      (node (ref "U2") (pin "4") (pinfunction "D-_4") (pintype "passive"))
    )
    (net (code "52") (name "/USB2_P") (class "Default")
      (node (ref "J1") (pin "105") (pinfunction "USB2-P_105") (pintype "passive"))
      (node (ref "U2") (pin "3") (pinfunction "D+_3") (pintype "passive"))
    )
    (net (code "53") (name "/USBH_N") (class "Default")
      (node (ref "U2") (pin "6") (pinfunction "HSD1-_6") (pintype "passive"))
      (node (ref "U5") (pin "29") (pinfunction "DMU_29") (pintype "passive"))
    )
    (net (code "54") (name "/USBH_P") (class "Default")
      (node (ref "U2") (pin "7") (pinfunction "HSD1+_7") (pintype "passive"))
      (node (ref "U5") (pin "30") (pinfunction "DPU_30") (pintype "passive"))
    )
    (net (code "55") (name "/VBUS") (class "Default")
      (node (ref "J3") (pin "1") (pinfunction "VCC_1") (pintype "passive"))
      (node (ref "R7") (pin "2") (pinfunction "2_2") (pintype "passive"))
    )
    (net (code "56") (name "/VD18_O") (class "Default")
      (node (ref "C1") (pin "1") (pinfunction "1_1") (pintype "passive"))
      (node (ref "C2") (pin "1") (pinfunction "1_1") (pintype "passive"))
      (node (ref "C3") (pin "1") (pinfunction "1_1") (pintype "passive"))
      (node (ref "U5") (pin "21") (pinfunction "VD_PLL_21") (pintype "passive"))
      (node (ref "U5") (pin "25") (pinfunction "VD18_O_25") (pintype "passive"))
      (node (ref "U5") (pin "28") (pinfunction "VD18_28") (pintype "passive"))
      (node (ref "U5") (pin "6") (pinfunction "VD18_6") (pintype "passive"))
    )
    (net (code "57") (name "/VD33_O") (class "Default")
      (node (ref "C14") (pin "1") (pinfunction "1_1") (pintype "passive"))
      (node (ref "C15") (pin "1") (pinfunction "1_1") (pintype "passive"))
      (node (ref "C17") (pin "1") (pinfunction "1_1") (pintype "passive"))
      (node (ref "C5") (pin "1") (pinfunction "1_1") (pintype "passive"))
      (node (ref "C6") (pin "1") (pinfunction "1_1") (pintype "passive"))
      (node (ref "C7") (pin "1") (pinfunction "1_1") (pintype "passive"))
      (node (ref "C8") (pin "1") (pinfunction "1_1") (pintype "passive"))
      (node (ref "U5") (pin "15") (pinfunction "VD33_15") (pintype "passive"))
      (node (ref "U5") (pin "20") (pinfunction "VD33_20") (pintype "passive"))
      (node (ref "U5") (pin "26") (pinfunction "VD33_26") (pintype "passive"))
      (node (ref "U5") (pin "31") (pinfunction "VD33_31") (pintype "passive"))
      (node (ref "U5") (pin "36") (pinfunction "VD33_36") (pintype "passive"))
      (node (ref "U5") (pin "42") (pinfunction "VD33_42") (pintype "passive"))
      (node (ref "U5") (pin "9") (pinfunction "VD33_O_9") (pintype "passive"))
    )
    (net (code "58") (name "/nEXT-RST") (class "Default")
      (node (ref "J1") (pin "100") (pinfunction "nEXTRST_100") (pintype "passive"))
      (node (ref "U5") (pin "40") (pinfunction "XRSTJ_40") (pintype "passive"))
    )
    (net (code "59") (name "/nPWR-LED") (class "Default")
      (node (ref "J1") (pin "95") (pinfunction "nRPI-LED-PWR_95") (pintype "passive"))
      (node (ref "U1") (pin "2") (pinfunction "2_2") (pintype "passive"))
    )
    (net (code "60") (name "3V3") (class "Default")
      (node (ref "C40") (pin "1") (pinfunction "1_1") (pintype "passive"))
      (node (ref "U24") (pin "13") (pinfunction "3.3V_13") (pintype "passive"))
    )
    (net (code "61") (name "AIN0") (class "Default")
      (node (ref "J1") (pin "96") (pinfunction "ANALOG-IP0_96") (pintype "passive"))
    )
    (net (code "62") (name "AIN1") (class "Default")
      (node (ref "J1") (pin "94") (pinfunction "ANALOG-IP1_94") (pintype "passive"))
    )
    (net (code "63") (name "BT-nDis") (class "Default")
      (node (ref "J1") (pin "91") (pinfunction "BT-nDisable_91") (pintype "passive"))
    )
    (net (code "64") (name "CAM-GPIO") (class "Default")
      (node (ref "J1") (pin "97") (pinfunction "CAMERA-GPIO_97") (pintype "passive"))
    )
    (net (code "65") (name "DISABLE_POE_DCDC") (class "Default")
      (node (ref "J1") (pin "48") (pinfunction "GPIO27_48") (pintype "passive"))
    )
    (net (code "66") (name "EEPROM-nWP") (class "Default")
      (node (ref "J1") (pin "20") (pinfunction "EEPROM-NWP_20") (pintype "passive"))
    )
    (net (code "67") (name "GND") (class "Default")
      (node (ref "C1") (pin "2") (pinfunction "2_2") (pintype "passive"))
      (node (ref "C10") (pin "2") (pinfunction "2_2") (pintype "passive"))
      (node (ref "C103") (pin "2") (pinfunction "2_2") (pintype "passive"))
      (node (ref "C104") (pin "2") (pinfunction "2_2") (pintype "passive"))
      (node (ref "C109") (pin "2") (pinfunction "2_2") (pintype "passive"))
      (node (ref "C110") (pin "2") (pinfunction "2_2") (pintype "passive"))
      (node (ref "C111") (pin "2") (pinfunction "2_2") (pintype "passive"))
      (node (ref "C112") (pin "-") (pinfunction "-_-") (pintype "passive"))
      (node (ref "C113") (pin "-") (pinfunction "-_-") (pintype "passive"))
      (node (ref "C114") (pin "-") (pinfunction "-_-") (pintype "passive"))
      (node (ref "C115") (pin "-") (pinfunction "-_-") (pintype "passive"))
      (node (ref "C116") (pin "-") (pinfunction "-_-") (pintype "passive"))
      (node (ref "C117") (pin "-") (pinfunction "-_-") (pintype "passive"))
      (node (ref "C14") (pin "2") (pinfunction "2_2") (pintype "passive"))
      (node (ref "C15") (pin "2") (pinfunction "2_2") (pintype "passive"))
      (node (ref "C16") (pin "2") (pinfunction "2_2") (pintype "passive"))
      (node (ref "C17") (pin "2") (pinfunction "2_2") (pintype "passive"))
      (node (ref "C19") (pin "2") (pinfunction "2_2") (pintype "passive"))
      (node (ref "C2") (pin "2") (pinfunction "2_2") (pintype "passive"))
      (node (ref "C20") (pin "2") (pinfunction "2_2") (pintype "passive"))
      (node (ref "C21") (pin "2") (pinfunction "2_2") (pintype "passive"))
      (node (ref "C3") (pin "2") (pinfunction "2_2") (pintype "passive"))
      (node (ref "C36") (pin "2") (pinfunction "2_2") (pintype "passive"))
      (node (ref "C37") (pin "2") (pinfunction "2_2") (pintype "passive"))
      (node (ref "C4") (pin "2") (pinfunction "2_2") (pintype "passive"))
      (node (ref "C40") (pin "2") (pinfunction "2_2") (pintype "passive"))
      (node (ref "C5") (pin "2") (pinfunction "2_2") (pintype "passive"))
      (node (ref "C6") (pin "2") (pinfunction "2_2") (pintype "passive"))
      (node (ref "C7") (pin "2") (pinfunction "2_2") (pintype "passive"))
      (node (ref "C8") (pin "2") (pinfunction "2_2") (pintype "passive"))
      (node (ref "C9") (pin "2") (pinfunction "2_2") (pintype "passive"))
      (node (ref "C93") (pin "2") (pinfunction "2_2") (pintype "passive"))
      (node (ref "D3") (pin "3") (pinfunction "GND_3_3") (pintype "passive"))
      (node (ref "D3") (pin "8") (pinfunction "GND_8_8") (pintype "passive"))
      (node (ref "FL1") (pin "B1") (pinfunction "GND_B1") (pintype "power_in"))
      (node (ref "FL2") (pin "B1") (pinfunction "GND_B1") (pintype "power_in"))
      (node (ref "FL3") (pin "B1") (pinfunction "GND_B1") (pintype "power_in"))
      (node (ref "FL4") (pin "B1") (pinfunction "GND_B1") (pintype "power_in"))
      (node (ref "FL8") (pin "B1") (pinfunction "GND_B1") (pintype "power_in"))
      (node (ref "FL9") (pin "B1") (pinfunction "GND_B1") (pintype "power_in"))
      (node (ref "J1") (pin "1") (pinfunction "GND_1") (pintype "passive"))
      (node (ref "J1") (pin "107") (pinfunction "GND_107") (pintype "passive"))
      (node (ref "J1") (pin "108") (pinfunction "GND_108") (pintype "passive"))
      (node (ref "J1") (pin "113") (pinfunction "GND_113") (pintype "passive"))
      (node (ref "J1") (pin "114") (pinfunction "GND_114") (pintype "passive"))
      (node (ref "J1") (pin "119") (pinfunction "GND_119") (pintype "passive"))
      (node (ref "J1") (pin "120") (pinfunction "GND_120") (pintype "passive"))
      (node (ref "J1") (pin "125") (pinfunction "GND_125") (pintype "passive"))
      (node (ref "J1") (pin "126") (pinfunction "GND_126") (pintype "passive"))
      (node (ref "J1") (pin "13") (pinfunction "GND_13") (pintype "passive"))
      (node (ref "J1") (pin "131") (pinfunction "GND_131") (pintype "passive"))
      (node (ref "J1") (pin "132") (pinfunction "GND_132") (pintype "passive"))
      (node (ref "J1") (pin "137") (pinfunction "GND_137") (pintype "passive"))
      (node (ref "J1") (pin "138") (pinfunction "GND_138") (pintype "passive"))
      (node (ref "J1") (pin "14") (pinfunction "GND_14") (pintype "passive"))
      (node (ref "J1") (pin "144") (pinfunction "GND_144") (pintype "passive"))
      (node (ref "J1") (pin "150") (pinfunction "GND_150") (pintype "passive"))
      (node (ref "J1") (pin "155") (pinfunction "GND_155") (pintype "passive"))
      (node (ref "J1") (pin "156") (pinfunction "GND_156") (pintype "passive"))
      (node (ref "J1") (pin "161") (pinfunction "GND_161") (pintype "passive"))
      (node (ref "J1") (pin "162") (pinfunction "GND_162") (pintype "passive"))
      (node (ref "J1") (pin "167") (pinfunction "GND_167") (pintype "passive"))
      (node (ref "J1") (pin "168") (pinfunction "GND_168") (pintype "passive"))
      (node (ref "J1") (pin "173") (pinfunction "GND_173") (pintype "passive"))
      (node (ref "J1") (pin "174") (pinfunction "GND_174") (pintype "passive"))
      (node (ref "J1") (pin "179") (pinfunction "GND_179") (pintype "passive"))
      (node (ref "J1") (pin "180") (pinfunction "GND_180") (pintype "passive"))
      (node (ref "J1") (pin "185") (pinfunction "GND_185") (pintype "passive"))
      (node (ref "J1") (pin "186") (pinfunction "GND_186") (pintype "passive"))
      (node (ref "J1") (pin "191") (pinfunction "GND_191") (pintype "passive"))
      (node (ref "J1") (pin "192") (pinfunction "GND_192") (pintype "passive"))
      (node (ref "J1") (pin "197") (pinfunction "GND_197") (pintype "passive"))
      (node (ref "J1") (pin "198") (pinfunction "GND_198") (pintype "passive"))
      (node (ref "J1") (pin "2") (pinfunction "GND_2") (pintype "passive"))
      (node (ref "J1") (pin "22") (pinfunction "GND_22") (pintype "passive"))
      (node (ref "J1") (pin "23") (pinfunction "GND_23") (pintype "passive"))
      (node (ref "J1") (pin "32") (pinfunction "GND_32") (pintype "passive"))
      (node (ref "J1") (pin "33") (pinfunction "GND_33") (pintype "passive"))
      (node (ref "J1") (pin "42") (pinfunction "GND_42") (pintype "passive"))
      (node (ref "J1") (pin "43") (pinfunction "GND_43") (pintype "passive"))
      (node (ref "J1") (pin "52") (pinfunction "GND_52") (pintype "passive"))
      (node (ref "J1") (pin "53") (pinfunction "GND_53") (pintype "passive"))
      (node (ref "J1") (pin "59") (pinfunction "GND_59") (pintype "passive"))
      (node (ref "J1") (pin "60") (pinfunction "GND_60") (pintype "passive"))
      (node (ref "J1") (pin "65") (pinfunction "GND_65") (pintype "passive"))
      (node (ref "J1") (pin "66") (pinfunction "GND_66") (pintype "passive"))
      (node (ref "J1") (pin "7") (pinfunction "GND_7") (pintype "passive"))
      (node (ref "J1") (pin "71") (pinfunction "GND_71") (pintype "passive"))
      (node (ref "J1") (pin "74") (pinfunction "GND_74") (pintype "passive"))
      (node (ref "J1") (pin "8") (pinfunction "GND_8") (pintype "passive"))
      (node (ref "J1") (pin "98") (pinfunction "GND_98") (pintype "passive"))
      (node (ref "J20") (pin "4") (pinfunction "GND_4") (pintype "passive"))
      (node (ref "J20") (pin "SH1") (pinfunction "SHIELD_SH1") (pintype "passive"))
      (node (ref "J20") (pin "SH2") (pinfunction "SHIELD_SH2") (pintype "passive"))
      (node (ref "J21") (pin "4") (pinfunction "GND_4") (pintype "passive"))
      (node (ref "J21") (pin "SH1") (pinfunction "SHIELD_SH1") (pintype "passive"))
      (node (ref "J21") (pin "SH2") (pinfunction "SHIELD_SH2") (pintype "passive"))
      (node (ref "J22") (pin "4") (pinfunction "GND_4") (pintype "passive"))
      (node (ref "J22") (pin "SH1") (pinfunction "SHIELD_SH1") (pintype "passive"))
      (node (ref "J22") (pin "SH2") (pinfunction "SHIELD_SH2") (pintype "passive"))
      (node (ref "J24") (pin "6") (pinfunction "VSS_6") (pintype "power_in"))
      (node (ref "J24") (pin "SH") (pinfunction "SHIELD_SH") (pintype "passive"))
      (node (ref "J25") (pin "1") (pinfunction "GND_1") (pintype "passive"))
      (node (ref "J25") (pin "3") (pinfunction "GND_3") (pintype "passive"))
      (node (ref "J3") (pin "5") (pinfunction "GND_5") (pintype "passive"))
      (node (ref "J3") (pin "SH") (pinfunction "SHIELD_SH") (pintype "passive"))
      (node (ref "J4") (pin "4") (pinfunction "GND_4") (pintype "passive"))
      (node (ref "J4") (pin "SH1") (pinfunction "SHIELD_SH1") (pintype "passive"))
      (node (ref "J4") (pin "SH2") (pinfunction "SHIELD_SH2") (pintype "passive"))
      (node (ref "J5") (pin "4") (pinfunction "GND_4") (pintype "passive"))
      (node (ref "J5") (pin "SH1") (pinfunction "SHIELD_SH1") (pintype "passive"))
      (node (ref "J5") (pin "SH2") (pinfunction "SHIELD_SH2") (pintype "passive"))
      (node (ref "J7") (pin "4") (pinfunction "GND_4") (pintype "passive"))
      (node (ref "J7") (pin "SH1") (pinfunction "SHIELD_SH1") (pintype "passive"))
      (node (ref "J7") (pin "SH2") (pinfunction "SHIELD_SH2") (pintype "passive"))
      (node (ref "R72") (pin "1") (pinfunction "1_1") (pintype "passive"))
      (node (ref "R74") (pin "1") (pinfunction "1_1") (pintype "passive"))
      (node (ref "R8") (pin "2") (pinfunction "2_2") (pintype "passive"))
      (node (ref "R9") (pin "2") (pinfunction "2_2") (pintype "passive"))
      (node (ref "U1") (pin "3") (pinfunction "3_3") (pintype "passive"))
      (node (ref "U17") (pin "2") (pinfunction "GND_2") (pintype "passive"))
      (node (ref "U18") (pin "2") (pinfunction "GND_2") (pintype "passive"))
      (node (ref "U19") (pin "2") (pinfunction "GND_2") (pintype "passive"))
      (node (ref "U2") (pin "10") (pinfunction "~{OE}_10") (pintype "passive"))
      (node (ref "U2") (pin "5") (pinfunction "GND_5") (pintype "passive"))
      (node (ref "U24") (pin "1") (pinfunction "GND_1") (pintype "passive"))
      (node (ref "U24") (pin "10") (pinfunction "GND_10") (pintype "passive"))
      (node (ref "U24") (pin "8") (pinfunction "GND_8") (pintype "passive"))
      (node (ref "U5") (pin "10") (pinfunction "VSS_10") (pintype "passive"))
      (node (ref "U5") (pin "24") (pinfunction "VSS_PLL_24") (pintype "passive"))
      (node (ref "U5") (pin "39") (pinfunction "VSS_39") (pintype "passive"))
    )
    (net (code "68") (name "Global-EN") (class "Default")
      (node (ref "J1") (pin "99") (pinfunction "GLOBAL-EN_99") (pintype "passive"))
    )
    (net (code "69") (name "HD7_N") (class "Default")
      (node (ref "U5") (pin "37") (pinfunction "DM7_37") (pintype "passive"))
    )
    (net (code "70") (name "HD7_P") (class "Default")
      (node (ref "U5") (pin "38") (pinfunction "DP7_38") (pintype "passive"))
    )
    (net (code "71") (name "ID-SC") (class "Default")
      (node (ref "J1") (pin "35") (pinfunction "ID-SC_35") (pintype "passive"))
    )
    (net (code "72") (name "ID-SD") (class "Default")
      (node (ref "J1") (pin "36") (pinfunction "ID-SD_36") (pintype "passive"))
    )
    (net (code "73") (name "IO4") (class "Default")
      (node (ref "J1") (pin "54") (pinfunction "GPIO4_54") (pintype "passive"))
    )
    (net (code "74") (name "IO5") (class "Default")
      (node (ref "J1") (pin "34") (pinfunction "GPIO5_34") (pintype "passive"))
    )
    (net (code "75") (name "IO8") (class "Default")
      (node (ref "J1") (pin "39") (pinfunction "GPIO8_39") (pintype "passive"))
    )
    (net (code "76") (name "IO9") (class "Default")
      (node (ref "J1") (pin "40") (pinfunction "GPIO9_40") (pintype "passive"))
    )
    (net (code "77") (name "IO10") (class "Default")
      (node (ref "J1") (pin "44") (pinfunction "GPIO10_44") (pintype "passive"))
    )
    (net (code "78") (name "IO11") (class "Default")
      (node (ref "J1") (pin "38") (pinfunction "GPIO11_38") (pintype "passive"))
    )
    (net (code "79") (name "IO13") (class "Default")
      (node (ref "J1") (pin "28") (pinfunction "GPIO13_28") (pintype "passive"))
    )
    (net (code "80") (name "IO14") (class "Default")
      (node (ref "J1") (pin "55") (pinfunction "GPIO14_55") (pintype "passive"))
    )
    (net (code "81") (name "IO15") (class "Default")
      (node (ref "J1") (pin "51") (pinfunction "GPIO15_51") (pintype "passive"))
    )
    (net (code "82") (name "IO16") (class "Default")
      (node (ref "J1") (pin "29") (pinfunction "GPIO16_29") (pintype "passive"))
    )
    (net (code "83") (name "IO17") (class "Default")
      (node (ref "J1") (pin "50") (pinfunction "GPIO17_50") (pintype "passive"))
    )
    (net (code "84") (name "LAN_RST") (class "Default")
      (node (ref "J1") (pin "30") (pinfunction "GPIO6_30") (pintype "passive"))
    )
    (net (code "85") (name "M.2_OFF{slash}ON") (class "Default")
      (node (ref "J1") (pin "45") (pinfunction "GPIO24_45") (pintype "passive"))
    )
    (net (code "86") (name "M.2_RST") (class "Default")
      (node (ref "J1") (pin "31") (pinfunction "GPIO12_31") (pintype "passive"))
    )
    (net (code "87") (name "M.2_W_DIS") (class "Default")
      (node (ref "J1") (pin "41") (pinfunction "GPIO25_41") (pintype "passive"))
    )
    (net (code "88") (name "Net-(D1-Pad2)") (class "Default")
      (node (ref "D1") (pin "2") (pinfunction "2_2") (pintype "passive"))
      (node (ref "R4") (pin "1") (pinfunction "1_1") (pintype "passive"))
    )
    (net (code "89") (name "Net-(D2-Pad2)") (class "Default")
      (node (ref "D2") (pin "2") (pinfunction "2_2") (pintype "passive"))
      (node (ref "R3") (pin "1") (pinfunction "1_1") (pintype "passive"))
    )
    (net (code "90") (name "Net-(J24-DET-A)") (class "Default")
      (node (ref "J24") (pin "10") (pinfunction "DET-A_10") (pintype "passive"))
      (node (ref "R49") (pin "1") (pinfunction "1_1") (pintype "passive"))
    )
    (net (code "91") (name "Net-(J24-DET-B)") (class "Default")
      (node (ref "J24") (pin "9") (pinfunction "DET-B_9") (pintype "power_in"))
      (node (ref "R89") (pin "1") (pinfunction "1_1") (pintype "passive"))
    )
    (net (code "92") (name "Net-(R4-Pad2)") (class "Default")
      (node (ref "R4") (pin "2") (pinfunction "2_2") (pintype "passive"))
      (node (ref "U1") (pin "4") (pinfunction "4_4") (pintype "passive"))
    )
    (net (code "93") (name "Net-(U5-REXT)") (class "Default")
      (node (ref "R9") (pin "1") (pinfunction "1_1") (pintype "passive"))
      (node (ref "U5") (pin "27") (pinfunction "REXT_27") (pintype "passive"))
    )
    (net (code "94") (name "Net-(U5-VBUSM)") (class "Default")
      (node (ref "R18") (pin "2") (pinfunction "2_2") (pintype "passive"))
      (node (ref "U5") (pin "41") (pinfunction "VBUSM_41") (pintype "passive"))
    )
    (net (code "95") (name "Net-(U5-XIN)") (class "Default")
      (node (ref "C9") (pin "1") (pinfunction "1_1") (pintype "passive"))
      (node (ref "U5") (pin "22") (pinfunction "XIN_22") (pintype "passive"))
      (node (ref "X1") (pin "2") (pinfunction "2_2") (pintype "passive"))
    )
    (net (code "96") (name "Net-(U5-XOUT)") (class "Default")
      (node (ref "C10") (pin "1") (pinfunction "1_1") (pintype "passive"))
      (node (ref "U5") (pin "23") (pinfunction "XOUT_23") (pintype "passive"))
      (node (ref "X1") (pin "1") (pinfunction "1_1") (pintype "passive"))
    )
    (net (code "97") (name "Net-(U17-ILIM)") (class "Default")
      (node (ref "R72") (pin "2") (pinfunction "2_2") (pintype "passive"))
      (node (ref "U17") (pin "5") (pinfunction "ILIM_5") (pintype "passive"))
    )
    (net (code "98") (name "Net-(U18-ILIM)") (class "Default")
      (node (ref "R74") (pin "2") (pinfunction "2_2") (pintype "passive"))
      (node (ref "U18") (pin "5") (pinfunction "ILIM_5") (pintype "passive"))
    )
    (net (code "99") (name "RUN-PG") (class "Default")
      (node (ref "J1") (pin "92") (pinfunction "RUN-PG_92") (pintype "passive"))
    )
    (net (code "100") (name "SCL0") (class "Default")
      (node (ref "J1") (pin "80") (pinfunction "SCL0_80") (pintype "passive"))
    )
    (net (code "101") (name "SCL1") (class "Default")
      (node (ref "J1") (pin "56") (pinfunction "GPIO3_56") (pintype "passive"))
    )
    (net (code "102") (name "SCL6") (class "Default")
      (node (ref "J1") (pin "47") (pinfunction "GPIO23_47") (pintype "passive"))
      (node (ref "R109") (pin "2") (pinfunction "2_2") (pintype "passive"))
    )
    (net (code "103") (name "SDA0") (class "Default")
      (node (ref "J1") (pin "82") (pinfunction "SDA0_82") (pintype "passive"))
    )
    (net (code "104") (name "SDA1") (class "Default")
      (node (ref "J1") (pin "58") (pinfunction "GPIO2_58") (pintype "passive"))
    )
    (net (code "105") (name "SDA6") (class "Default")
      (node (ref "J1") (pin "46") (pinfunction "GPIO22_46") (pintype "passive"))
      (node (ref "R108") (pin "2") (pinfunction "2_2") (pintype "passive"))
    )
    (net (code "106") (name "SYNC-IN") (class "Default")
      (node (ref "J1") (pin "16") (pinfunction "ETH-SYNC-IN(1.8v)_16") (pintype "passive"))
    )
    (net (code "107") (name "SYNC-OUT") (class "Default")
      (node (ref "J1") (pin "18") (pinfunction "ETH-SYNC-OUT(1.8v)_18") (pintype "passive"))
    )
    (net (code "108") (name "TRD3_0_N") (class "Default")
      (node (ref "J1") (pin "10") (pinfunction "ETH-PAIR-0-N_10") (pintype "passive"))
    )
    (net (code "109") (name "TRD3_0_P") (class "Default")
      (node (ref "J1") (pin "12") (pinfunction "ETH-PAIR-0-P_12") (pintype "passive"))
    )
    (net (code "110") (name "TRD3_1_N") (class "Default")
      (node (ref "J1") (pin "6") (pinfunction "ETH-PAIR-1-N_6") (pintype "passive"))
    )
    (net (code "111") (name "TRD3_1_P") (class "Default")
      (node (ref "J1") (pin "4") (pinfunction "ETH-PAIR-1-P_4") (pintype "passive"))
    )
    (net (code "112") (name "TRD3_2_N") (class "Default")
      (node (ref "J1") (pin "9") (pinfunction "ETH-PAIR-2-N_9") (pintype "passive"))
    )
    (net (code "113") (name "TRD3_2_P") (class "Default")
      (node (ref "J1") (pin "11") (pinfunction "ETH-PAIR-2-P_11") (pintype "passive"))
    )
    (net (code "114") (name "TRD3_3_N") (class "Default")
      (node (ref "J1") (pin "3") (pinfunction "ETH-PAIR-3-P_3") (pintype "passive"))
    )
    (net (code "115") (name "TRD3_3_P") (class "Default")
      (node (ref "J1") (pin "5") (pinfunction "ETH-PAIR-3-N_5") (pintype "passive"))
    )
    (net (code "116") (name "TV-OUT") (class "Default")
      (node (ref "J1") (pin "111") (pinfunction "VDAC-COMP_111") (pintype "passive"))
    )
    (net (code "117") (name "T{slash}R") (class "Default")
      (node (ref "J1") (pin "37") (pinfunction "GPIO7_37") (pintype "passive"))
    )
    (net (code "118") (name "VB1") (class "Default")
      (node (ref "C112") (pin "+") (pinfunction "+_+") (pintype "passive"))
      (node (ref "C113") (pin "+") (pinfunction "+_+") (pintype "passive"))
      (node (ref "C114") (pin "+") (pinfunction "+_+") (pintype "passive"))
      (node (ref "C20") (pin "1") (pinfunction "1_1") (pintype "passive"))
      (node (ref "C21") (pin "1") (pinfunction "1_1") (pintype "passive"))
      (node (ref "J4") (pin "1") (pinfunction "VBUS_1") (pintype "passive"))
      (node (ref "J5") (pin "1") (pinfunction "VBUS_1") (pintype "passive"))
      (node (ref "J7") (pin "1") (pinfunction "VBUS_1") (pintype "passive"))
      (node (ref "U17") (pin "6") (pinfunction "OUT_6") (pintype "passive"))
    )
    (net (code "119") (name "VB2") (class "Default")
      (node (ref "C109") (pin "1") (pinfunction "1_1") (pintype "passive"))
      (node (ref "C110") (pin "1") (pinfunction "1_1") (pintype "passive"))
      (node (ref "C115") (pin "+") (pinfunction "+_+") (pintype "passive"))
      (node (ref "C116") (pin "+") (pinfunction "+_+") (pintype "passive"))
      (node (ref "C117") (pin "+") (pinfunction "+_+") (pintype "passive"))
      (node (ref "J20") (pin "1") (pinfunction "VBUS_1") (pintype "passive"))
      (node (ref "J21") (pin "1") (pinfunction "VBUS_1") (pintype "passive"))
      (node (ref "J22") (pin "1") (pinfunction "VBUS_1") (pintype "passive"))
      (node (ref "U18") (pin "6") (pinfunction "OUT_6") (pintype "passive"))
    )
    (net (code "120") (name "WL-nDis") (class "Default")
      (node (ref "J1") (pin "89") (pinfunction "WL-nDisable_89") (pintype "passive"))
    )
    (net (code "121") (name "nRPI-BOOT") (class "Default")
      (node (ref "J1") (pin "93") (pinfunction "nRPI-BOOT_93") (pintype "passive"))
    )
    (net (code "122") (name "unconnected-(D3-D1+-Pad1)") (class "Default")
      (node (ref "D3") (pin "1") (pinfunction "D1+_1") (pintype "passive+no_connect"))
    )
    (net (code "123") (name "unconnected-(D3-D1--Pad2)") (class "Default")
      (node (ref "D3") (pin "2") (pinfunction "D1-_2") (pintype "passive+no_connect"))
    )
    (net (code "124") (name "unconnected-(J1A-ETH-nLED1(3.3v)-Pad19)") (class "Default")
      (node (ref "J1") (pin "19") (pinfunction "ETH-nLED1(3.3v)_19") (pintype "passive+no_connect"))
    )
    (net (code "125") (name "unconnected-(J1A-ETH-nLED2(3.3v)-Pad17)") (class "Default")
      (node (ref "J1") (pin "17") (pinfunction "ETH-nLED2(3.3v)_17") (pintype "passive+no_connect"))
    )
    (net (code "126") (name "unconnected-(J1A-ETH-nLED3(3.3v)-Pad15)") (class "Default")
      (node (ref "J1") (pin "15") (pinfunction "ETH-nLED3(3.3v)_15") (pintype "passive+no_connect"))
    )
    (net (code "127") (name "unconnected-(J1A-SD-DATA4-Pad68)") (class "Default")
      (node (ref "J1") (pin "68") (pinfunction "SD-DATA4_68") (pintype "passive+no_connect"))
    )
    (net (code "128") (name "unconnected-(J1A-SD-DATA5-Pad64)") (class "Default")
      (node (ref "J1") (pin "64") (pinfunction "SD-DATA5_64") (pintype "passive+no_connect"))
    )
    (net (code "129") (name "unconnected-(J1A-SD-DATA6-Pad72)") (class "Default")
      (node (ref "J1") (pin "72") (pinfunction "SD-DATA6_72") (pintype "passive+no_connect"))
    )
    (net (code "130") (name "unconnected-(J1A-SD-DATA7-Pad70)") (class "Default")
      (node (ref "J1") (pin "70") (pinfunction "SD-DATA7_70") (pintype "passive+no_connect"))
    )
    (net (code "131") (name "unconnected-(J1A-SD-VDD-Override-Pad73)") (class "Default")
      (node (ref "J1") (pin "73") (pinfunction "SD-VDD-Override_73") (pintype "passive+no_connect"))
    )
    (net (code "132") (name "unconnected-(J1B-CAM0-C-N-Pad140)") (class "Default")
      (node (ref "J1") (pin "140") (pinfunction "CAM0-C-N_140") (pintype "passive+no_connect"))
    )
    (net (code "133") (name "unconnected-(J1B-CAM0-C-P-Pad142)") (class "Default")
      (node (ref "J1") (pin "142") (pinfunction "CAM0-C-P_142") (pintype "passive+no_connect"))
    )
    (net (code "134") (name "unconnected-(J1B-CAM0-D0-N-Pad128)") (class "Default")
      (node (ref "J1") (pin "128") (pinfunction "CAM0-D0-N_128") (pintype "passive+no_connect"))
    )
    (net (code "135") (name "unconnected-(J1B-CAM0-D0-P-Pad130)") (class "Default")
      (node (ref "J1") (pin "130") (pinfunction "CAM0-D0-P_130") (pintype "passive+no_connect"))
    )
    (net (code "136") (name "unconnected-(J1B-CAM0-D1-N-Pad134)") (class "Default")
      (node (ref "J1") (pin "134") (pinfunction "CAM0-D1-N_134") (pintype "passive+no_connect"))
    )
    (net (code "137") (name "unconnected-(J1B-CAM0-D1-P-Pad136)") (class "Default")
      (node (ref "J1") (pin "136") (pinfunction "CAM0-D1-P_136") (pintype "passive+no_connect"))
    )
    (net (code "138") (name "unconnected-(J1B-CAM1-C-N-Pad127)") (class "Default")
      (node (ref "J1") (pin "127") (pinfunction "CAM1-C-N_127") (pintype "passive+no_connect"))
    )
    (net (code "139") (name "unconnected-(J1B-CAM1-C-P-Pad129)") (class "Default")
      (node (ref "J1") (pin "129") (pinfunction "CAM1-C-P_129") (pintype "passive+no_connect"))
    )
    (net (code "140") (name "unconnected-(J1B-CAM1-D0-N-Pad115)") (class "Default")
      (node (ref "J1") (pin "115") (pinfunction "CAM1-D0-N_115") (pintype "passive+no_connect"))
    )
    (net (code "141") (name "unconnected-(J1B-CAM1-D0-P-Pad117)") (class "Default")
      (node (ref "J1") (pin "117") (pinfunction "CAM1-D0-P_117") (pintype "passive+no_connect"))
    )
    (net (code "142") (name "unconnected-(J1B-CAM1-D1-N-Pad121)") (class "Default")
      (node (ref "J1") (pin "121") (pinfunction "CAM1-D1-N_121") (pintype "passive+no_connect"))
    )
    (net (code "143") (name "unconnected-(J1B-CAM1-D1-P-Pad123)") (class "Default")
      (node (ref "J1") (pin "123") (pinfunction "CAM1-D1-P_123") (pintype "passive+no_connect"))
    )
    (net (code "144") (name "unconnected-(J1B-CAM1-D2-N-Pad133)") (class "Default")
      (node (ref "J1") (pin "133") (pinfunction "CAM1-D2-N_133") (pintype "passive+no_connect"))
    )
    (net (code "145") (name "unconnected-(J1B-CAM1-D2-P-Pad135)") (class "Default")
      (node (ref "J1") (pin "135") (pinfunction "CAM1-D2-P_135") (pintype "passive+no_connect"))
    )
    (net (code "146") (name "unconnected-(J1B-CAM1-D3-N-Pad139)") (class "Default")
      (node (ref "J1") (pin "139") (pinfunction "CAM1-D3-N_139") (pintype "passive"))
    )
    (net (code "147") (name "unconnected-(J1B-CAM1-D3-P-Pad141)") (class "Default")
      (node (ref "J1") (pin "141") (pinfunction "CAM1-D3-P_141") (pintype "passive"))
    )
    (net (code "148") (name "unconnected-(J1B-DS1-D3-N-Pad194)") (class "Default")
      (node (ref "J1") (pin "194") (pinfunction "DS1-D3-N_194") (pintype "passive+no_connect"))
    )
    (net (code "149") (name "unconnected-(J1B-DS1-D3-P-Pad196)") (class "Default")
      (node (ref "J1") (pin "196") (pinfunction "DS1-D3-P_196") (pintype "passive+no_connect"))
    )
    (net (code "150") (name "unconnected-(J1B-DSI0-C-N-Pad169)") (class "Default")
      (node (ref "J1") (pin "169") (pinfunction "DSI0-C-N_169") (pintype "passive+no_connect"))
    )
    (net (code "151") (name "unconnected-(J1B-DSI0-C-P-Pad171)") (class "Default")
      (node (ref "J1") (pin "171") (pinfunction "DSI0-C-P_171") (pintype "passive+no_connect"))
    )
    (net (code "152") (name "unconnected-(J1B-DSI0-D0-N-Pad157)") (class "Default")
      (node (ref "J1") (pin "157") (pinfunction "DSI0-D0-N_157") (pintype "passive+no_connect"))
    )
    (net (code "153") (name "unconnected-(J1B-DSI0-D0-P-Pad159)") (class "Default")
      (node (ref "J1") (pin "159") (pinfunction "DSI0-D0-P_159") (pintype "passive+no_connect"))
    )
    (net (code "154") (name "unconnected-(J1B-DSI0-D1-N-Pad163)") (class "Default")
      (node (ref "J1") (pin "163") (pinfunction "DSI0-D1-N_163") (pintype "passive+no_connect"))
    )
    (net (code "155") (name "unconnected-(J1B-DSI0-D1-P-Pad165)") (class "Default")
      (node (ref "J1") (pin "165") (pinfunction "DSI0-D1-P_165") (pintype "passive+no_connect"))
    )
    (net (code "156") (name "unconnected-(J1B-DSI1-C-N-Pad187)") (class "Default")
      (node (ref "J1") (pin "187") (pinfunction "DSI1-C-N_187") (pintype "passive+no_connect"))
    )
    (net (code "157") (name "unconnected-(J1B-DSI1-C-P-Pad189)") (class "Default")
      (node (ref "J1") (pin "189") (pinfunction "DSI1-C-P_189") (pintype "passive+no_connect"))
    )
    (net (code "158") (name "unconnected-(J1B-DSI1-D0-N-Pad175)") (class "Default")
      (node (ref "J1") (pin "175") (pinfunction "DSI1-D0-N_175") (pintype "passive+no_connect"))
    )
    (net (code "159") (name "unconnected-(J1B-DSI1-D0-P-Pad177)") (class "Default")
      (node (ref "J1") (pin "177") (pinfunction "DSI1-D0-P_177") (pintype "passive+no_connect"))
    )
    (net (code "160") (name "unconnected-(J1B-DSI1-D1-N-Pad181)") (class "Default")
      (node (ref "J1") (pin "181") (pinfunction "DSI1-D1-N_181") (pintype "passive+no_connect"))
    )
    (net (code "161") (name "unconnected-(J1B-DSI1-D1-P-Pad183)") (class "Default")
      (node (ref "J1") (pin "183") (pinfunction "DSI1-D1-P_183") (pintype "passive+no_connect"))
    )
    (net (code "162") (name "unconnected-(J1B-DSI1-D2-N-Pad193)") (class "Default")
      (node (ref "J1") (pin "193") (pinfunction "DSI1-D2-N_193") (pintype "passive+no_connect"))
    )
    (net (code "163") (name "unconnected-(J1B-DSI1-D2-N-Pad195)") (class "Default")
      (node (ref "J1") (pin "195") (pinfunction "DSI1-D2-N_195") (pintype "passive+no_connect"))
    )
    (net (code "164") (name "unconnected-(J1B-HDMI0-CEC-Pad151)") (class "Default")
      (node (ref "J1") (pin "151") (pinfunction "HDMI0-CEC_151") (pintype "passive+no_connect"))
    )
    (net (code "165") (name "unconnected-(J1B-HDMI0-CLK-N-Pad190)") (class "Default")
      (node (ref "J1") (pin "190") (pinfunction "HDMI0-CLK-N_190") (pintype "passive+no_connect"))
    )
    (net (code "166") (name "unconnected-(J1B-HDMI0-CLK-P-Pad188)") (class "Default")
      (node (ref "J1") (pin "188") (pinfunction "HDMI0-CLK-P_188") (pintype "passive+no_connect"))
    )
    (net (code "167") (name "unconnected-(J1B-HDMI0-HotPlug-Pad153)") (class "Default")
      (node (ref "J1") (pin "153") (pinfunction "HDMI0-HotPlug_153") (pintype "passive+no_connect"))
    )
    (net (code "168") (name "unconnected-(J1B-HDMI0-SCL-Pad200)") (class "Default")
      (node (ref "J1") (pin "200") (pinfunction "HDMI0-SCL_200") (pintype "passive+no_connect"))
    )
    (net (code "169") (name "unconnected-(J1B-HDMI0-SDA-Pad199)") (class "Default")
      (node (ref "J1") (pin "199") (pinfunction "HDMI0-SDA_199") (pintype "passive+no_connect"))
    )
    (net (code "170") (name "unconnected-(J1B-HDMI0-TX0-N-Pad184)") (class "Default")
      (node (ref "J1") (pin "184") (pinfunction "HDMI0-TX0-N_184") (pintype "passive+no_connect"))
    )
    (net (code "171") (name "unconnected-(J1B-HDMI0-TX0-P-Pad182)") (class "Default")
      (node (ref "J1") (pin "182") (pinfunction "HDMI0-TX0-P_182") (pintype "passive+no_connect"))
    )
    (net (code "172") (name "unconnected-(J1B-HDMI0-TX1-N-Pad178)") (class "Default")
      (node (ref "J1") (pin "178") (pinfunction "HDMI0-TX1-N_178") (pintype "passive+no_connect"))
    )
    (net (code "173") (name "unconnected-(J1B-HDMI0-TX1-P-Pad176)") (class "Default")
      (node (ref "J1") (pin "176") (pinfunction "HDMI0-TX1-P_176") (pintype "passive+no_connect"))
    )
    (net (code "174") (name "unconnected-(J1B-HDMI0-TX2-N-Pad172)") (class "Default")
      (node (ref "J1") (pin "172") (pinfunction "HDMI0-TX2-N_172") (pintype "passive+no_connect"))
    )
    (net (code "175") (name "unconnected-(J1B-HDMI0-TX2-P-Pad170)") (class "Default")
      (node (ref "J1") (pin "170") (pinfunction "HDMI0-TX2-P_170") (pintype "passive+no_connect"))
    )
    (net (code "176") (name "unconnected-(J1B-HDMI1-CEC-Pad149)") (class "Default")
      (node (ref "J1") (pin "149") (pinfunction "HDMI1-CEC_149") (pintype "passive+no_connect"))
    )
    (net (code "177") (name "unconnected-(J1B-HDMI1-CLK-N-Pad166)") (class "Default")
      (node (ref "J1") (pin "166") (pinfunction "HDMI1-CLK-N_166") (pintype "passive+no_connect"))
    )
    (net (code "178") (name "unconnected-(J1B-HDMI1-CLK-P-Pad164)") (class "Default")
      (node (ref "J1") (pin "164") (pinfunction "HDMI1-CLK-P_164") (pintype "passive+no_connect"))
    )
    (net (code "179") (name "unconnected-(J1B-HDMI1-HotPlug-Pad143)") (class "Default")
      (node (ref "J1") (pin "143") (pinfunction "HDMI1-HotPlug_143") (pintype "passive+no_connect"))
    )
    (net (code "180") (name "unconnected-(J1B-HDMI1-SCL-Pad147)") (class "Default")
      (node (ref "J1") (pin "147") (pinfunction "HDMI1-SCL_147") (pintype "passive+no_connect"))
    )
    (net (code "181") (name "unconnected-(J1B-HDMI1-SDA-Pad145)") (class "Default")
      (node (ref "J1") (pin "145") (pinfunction "HDMI1-SDA_145") (pintype "passive+no_connect"))
    )
    (net (code "182") (name "unconnected-(J1B-HDMI1-TX0-N-Pad160)") (class "Default")
      (node (ref "J1") (pin "160") (pinfunction "HDMI1-TX0-N_160") (pintype "passive+no_connect"))
    )
    (net (code "183") (name "unconnected-(J1B-HDMI1-TX0-P-Pad158)") (class "Default")
      (node (ref "J1") (pin "158") (pinfunction "HDMI1-TX0-P_158") (pintype "passive+no_connect"))
    )
    (net (code "184") (name "unconnected-(J1B-HDMI1-TX1-N-Pad154)") (class "Default")
      (node (ref "J1") (pin "154") (pinfunction "HDMI1-TX1-N_154") (pintype "passive+no_connect"))
    )
    (net (code "185") (name "unconnected-(J1B-HDMI1-TX1-P-Pad152)") (class "Default")
      (node (ref "J1") (pin "152") (pinfunction "HDMI1-TX1-P_152") (pintype "passive+no_connect"))
    )
    (net (code "186") (name "unconnected-(J1B-HDMI1-TX2-N-Pad148)") (class "Default")
      (node (ref "J1") (pin "148") (pinfunction "HDMI1-TX2-N_148") (pintype "passive+no_connect"))
    )
    (net (code "187") (name "unconnected-(J1B-HDMI1-TX2-P-Pad146)") (class "Default")
      (node (ref "J1") (pin "146") (pinfunction "HDMI1-TX2-P_146") (pintype "passive+no_connect"))
    )
    (net (code "188") (name "unconnected-(J1B-PCIe-CLK-N-Pad112)") (class "Default")
      (node (ref "J1") (pin "112") (pinfunction "PCIe-CLK-N_112") (pintype "passive+no_connect"))
    )
    (net (code "189") (name "unconnected-(J1B-PCIe-CLK-P-Pad110)") (class "Default")
      (node (ref "J1") (pin "110") (pinfunction "PCIe-CLK-P_110") (pintype "passive+no_connect"))
    )
    (net (code "190") (name "unconnected-(J1B-PCIe-CLK-nREQ-Pad102)") (class "Default")
      (node (ref "J1") (pin "102") (pinfunction "PCIe-CLK-nREQ_102") (pintype "passive+no_connect"))
    )
    (net (code "191") (name "unconnected-(J1B-PCIe-RX-N-Pad118)") (class "Default")
      (node (ref "J1") (pin "118") (pinfunction "PCIe-RX-N_118") (pintype "passive+no_connect"))
    )
    (net (code "192") (name "unconnected-(J1B-PCIe-RX-P-Pad116)") (class "Default")
      (node (ref "J1") (pin "116") (pinfunction "PCIe-RX-P_116") (pintype "passive+no_connect"))
    )
    (net (code "193") (name "unconnected-(J1B-PCIe-TX-N-Pad124)") (class "Default")
      (node (ref "J1") (pin "124") (pinfunction "PCIe-TX-N_124") (pintype "passive+no_connect"))
    )
    (net (code "194") (name "unconnected-(J1B-PCIe-TX-P-Pad122)") (class "Default")
      (node (ref "J1") (pin "122") (pinfunction "PCIe-TX-P_122") (pintype "passive+no_connect"))
    )
    (net (code "195") (name "unconnected-(J1B-PCIe-nRST-Pad109)") (class "Default")
      (node (ref "J1") (pin "109") (pinfunction "PCIe-nRST_109") (pintype "passive+no_connect"))
    )
    (net (code "196") (name "unconnected-(J1B-Reserved-Pad104)") (class "Default")
      (node (ref "J1") (pin "104") (pinfunction "Reserved_104") (pintype "passive+no_connect"))
    )
    (net (code "197") (name "unconnected-(J1B-Reserved-Pad106)") (class "Default")
      (node (ref "J1") (pin "106") (pinfunction "Reserved_106") (pintype "passive+no_connect"))
    )
    (net (code "198") (name "unconnected-(J3-ID-Pad4)") (class "Default")
      (node (ref "J3") (pin "4") (pinfunction "ID_4") (pintype "passive+no_connect"))
    )
    (net (code "199") (name "unconnected-(U1-Pad1)") (class "Default")
      (node (ref "U1") (pin "1") (pinfunction "1_1") (pintype "passive+no_connect"))
    )
    (net (code "200") (name "unconnected-(U5-DRV-Pad1)") (class "Default")
      (node (ref "U5") (pin "1") (pinfunction "DRV_1") (pintype "passive+no_connect"))
    )
    (net (code "201") (name "unconnected-(U5-LED[1]-Pad3)") (class "Default")
      (node (ref "U5") (pin "3") (pinfunction "LED[1]_3") (pintype "passive+no_connect"))
    )
    (net (code "202") (name "unconnected-(U5-LED[2]-Pad4)") (class "Default")
      (node (ref "U5") (pin "4") (pinfunction "LED[2]_4") (pintype "passive+no_connect"))
    )
    (net (code "203") (name "unconnected-(U5-LED[3]-Pad5)") (class "Default")
      (node (ref "U5") (pin "5") (pinfunction "LED[3]_5") (pintype "passive+no_connect"))
    )
    (net (code "204") (name "unconnected-(U5-LED[4]-Pad7)") (class "Default")
      (node (ref "U5") (pin "7") (pinfunction "LED[4]_7") (pintype "passive+no_connect"))
    )
    (net (code "205") (name "unconnected-(U5-LED[5]-Pad48)") (class "Default")
      (node (ref "U5") (pin "48") (pinfunction "LED[5]_48") (pintype "passive+no_connect"))
    )
    (net (code "206") (name "unconnected-(U5-TESTJ-Pad2)") (class "Default")
      (node (ref "U5") (pin "2") (pinfunction "TESTJ_2") (pintype "passive+no_connect"))
    )
    (net (code "207") (name "unconnected-(U19-nFLG-Pad3)") (class "Default")
      (node (ref "U19") (pin "3") (pinfunction "nFLG_3") (pintype "passive+no_connect"))
    )
    (net (code "208") (name "unconnected-(U24-DIO0-Pad14)") (class "Default")
      (node (ref "U24") (pin "14") (pinfunction "DIO0_14") (pintype "passive+no_connect"))
    )
    (net (code "209") (name "unconnected-(U24-DIO1-Pad15)") (class "Default")
      (node (ref "U24") (pin "15") (pinfunction "DIO1_15") (pintype "passive+no_connect"))
    )
    (net (code "210") (name "unconnected-(U24-DIO2-Pad16)") (class "Default")
      (node (ref "U24") (pin "16") (pinfunction "DIO2_16") (pintype "passive+no_connect"))
    )
    (net (code "211") (name "unconnected-(U24-DIO3-Pad11)") (class "Default")
      (node (ref "U24") (pin "11") (pinfunction "DIO3_11") (pintype "passive+no_connect"))
    )
    (net (code "212") (name "unconnected-(U24-DIO4-Pad12)") (class "Default")
      (node (ref "U24") (pin "12") (pinfunction "DIO4_12") (pintype "passive+no_connect"))
    )
    (net (code "213") (name "unconnected-(U24-DIO5-Pad7)") (class "Default")
      (node (ref "U24") (pin "7") (pinfunction "DIO5_7") (pintype "passive+no_connect"))
    )
  )
)
